# SeismicAccelerometerSystem.net
KiCad netlist of a schematic drawn in EAGLE
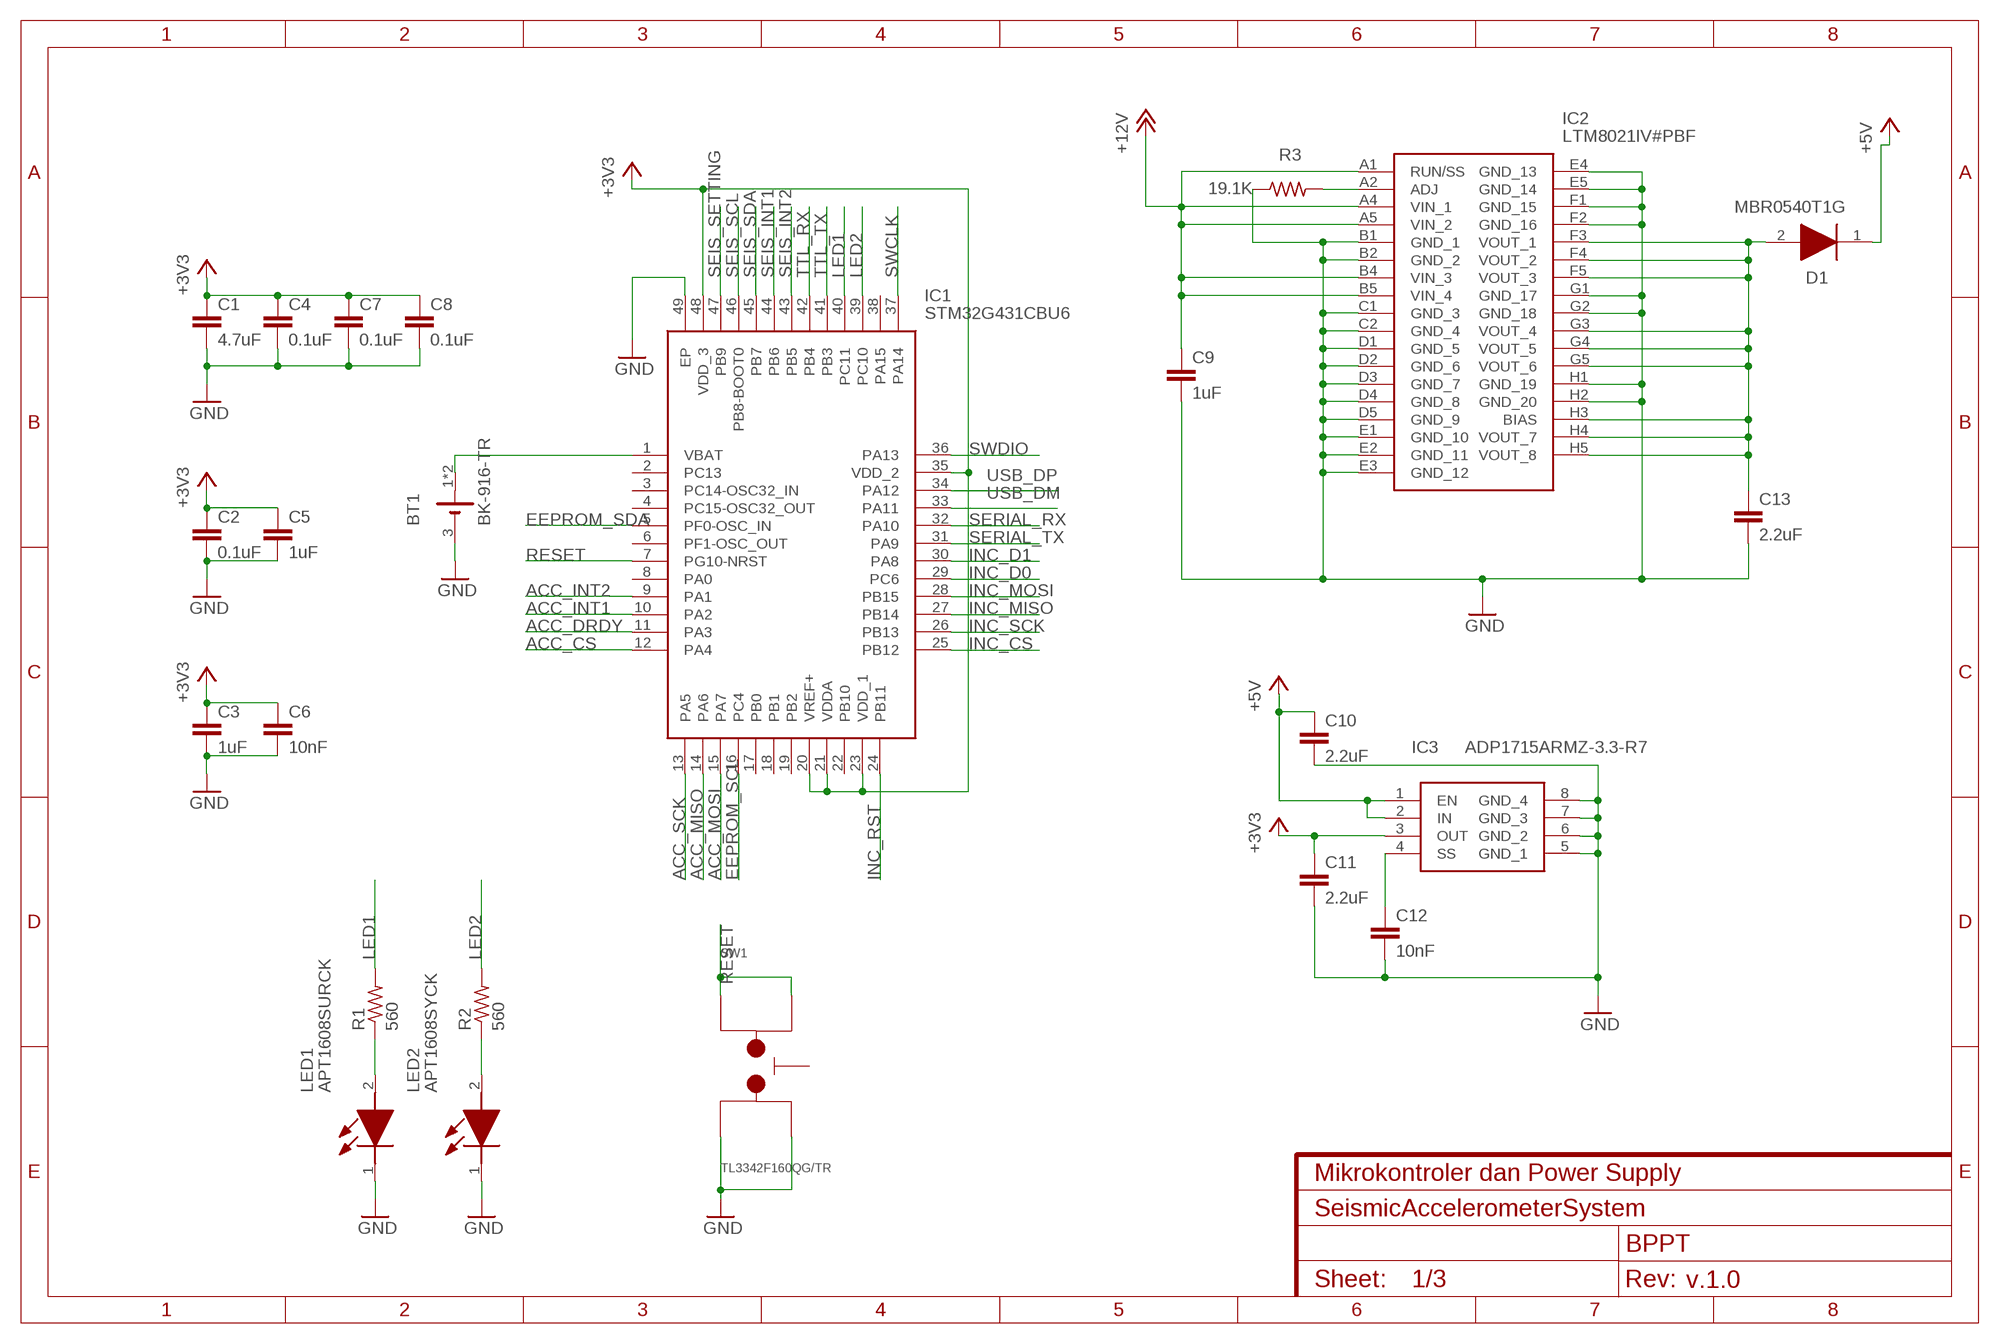
[diagram p0: schematic, sheet 1]
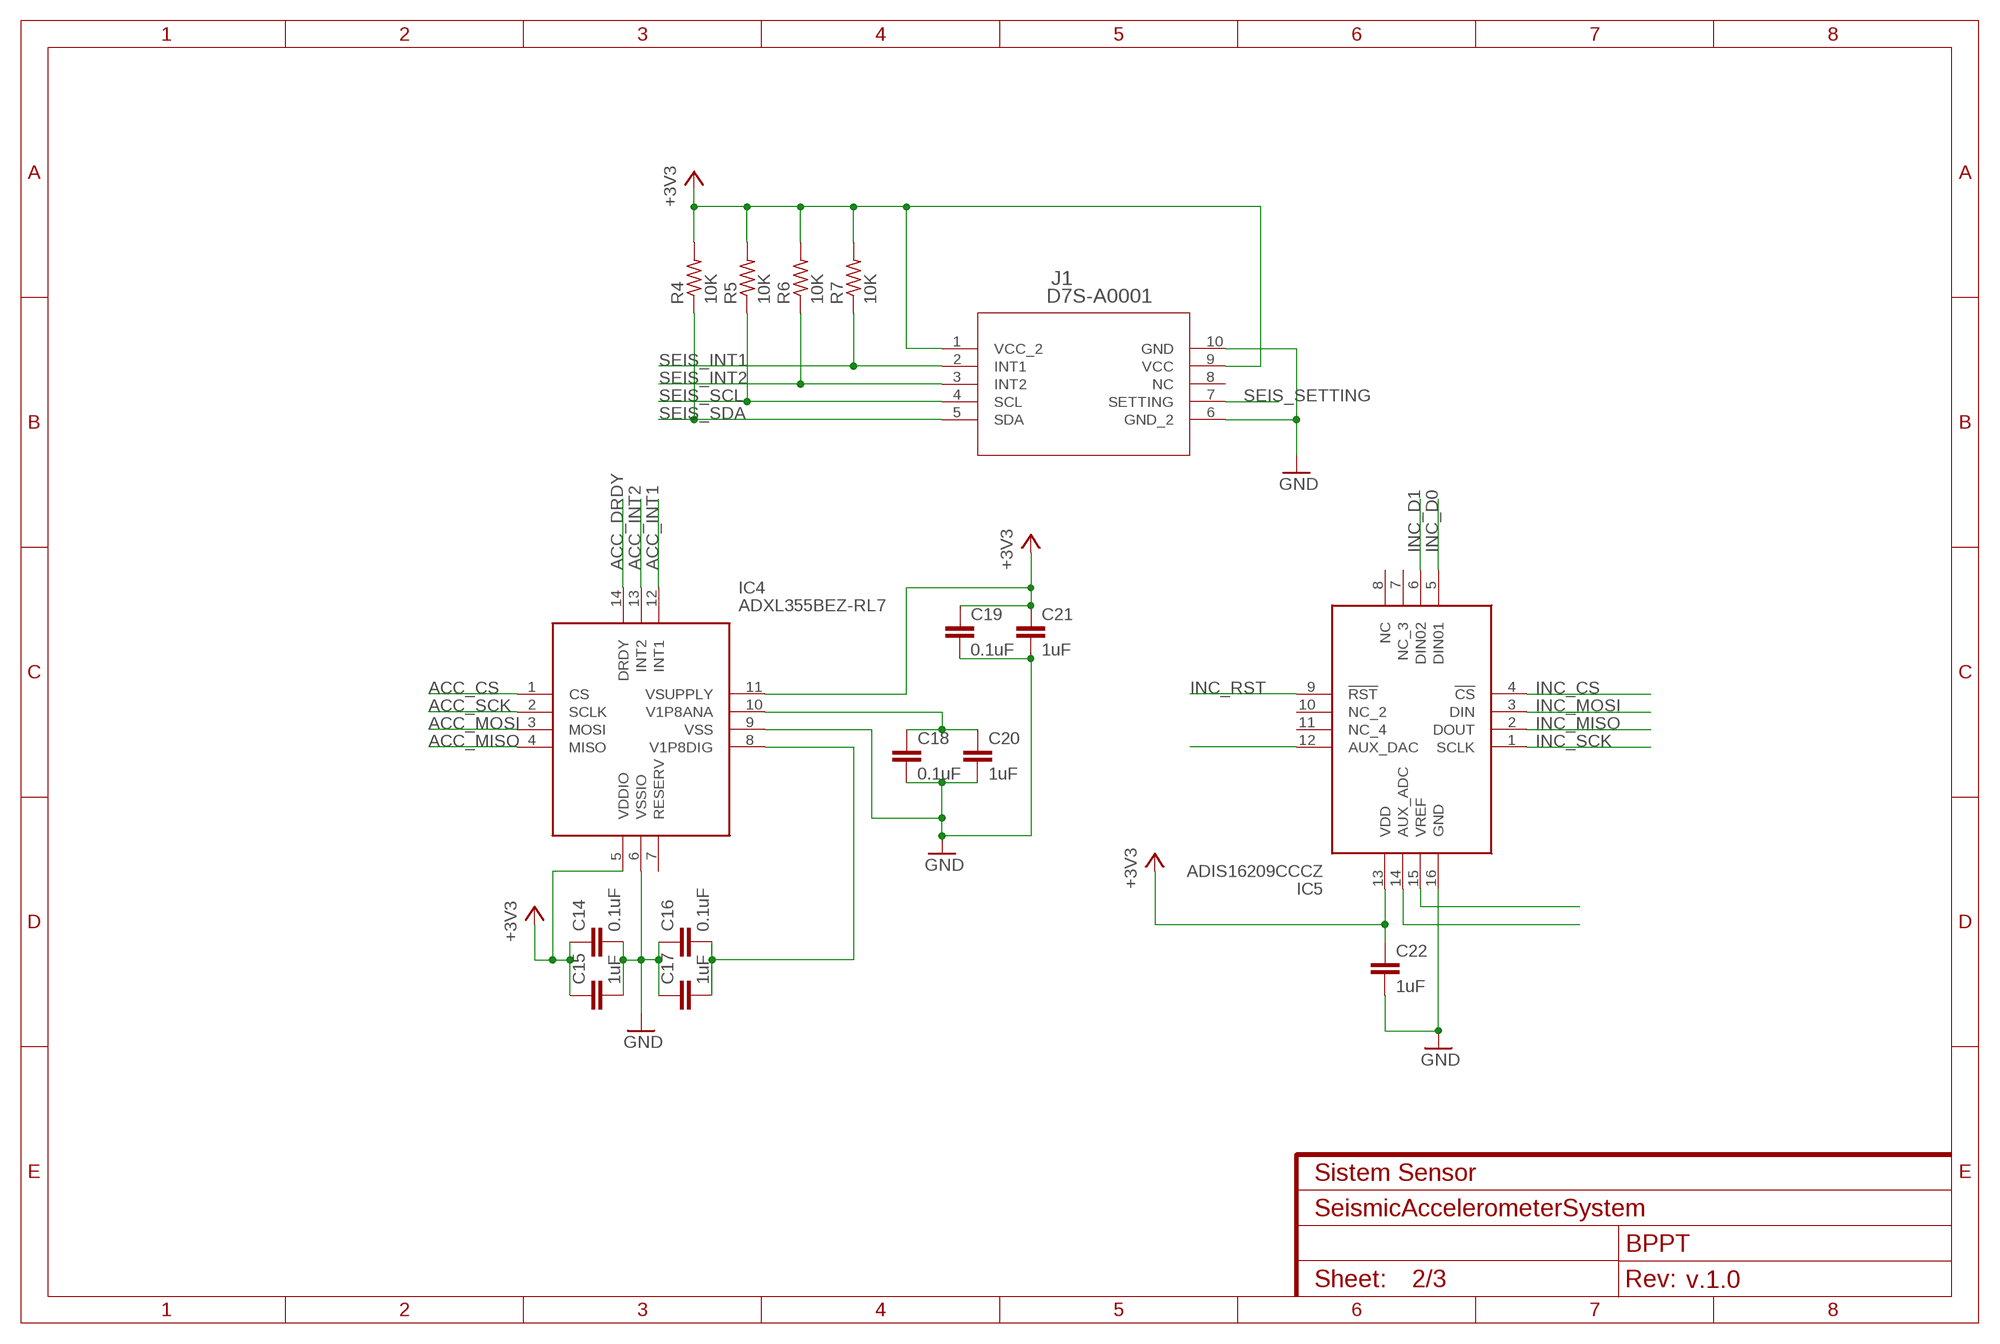
[diagram p1: schematic, sheet 2]
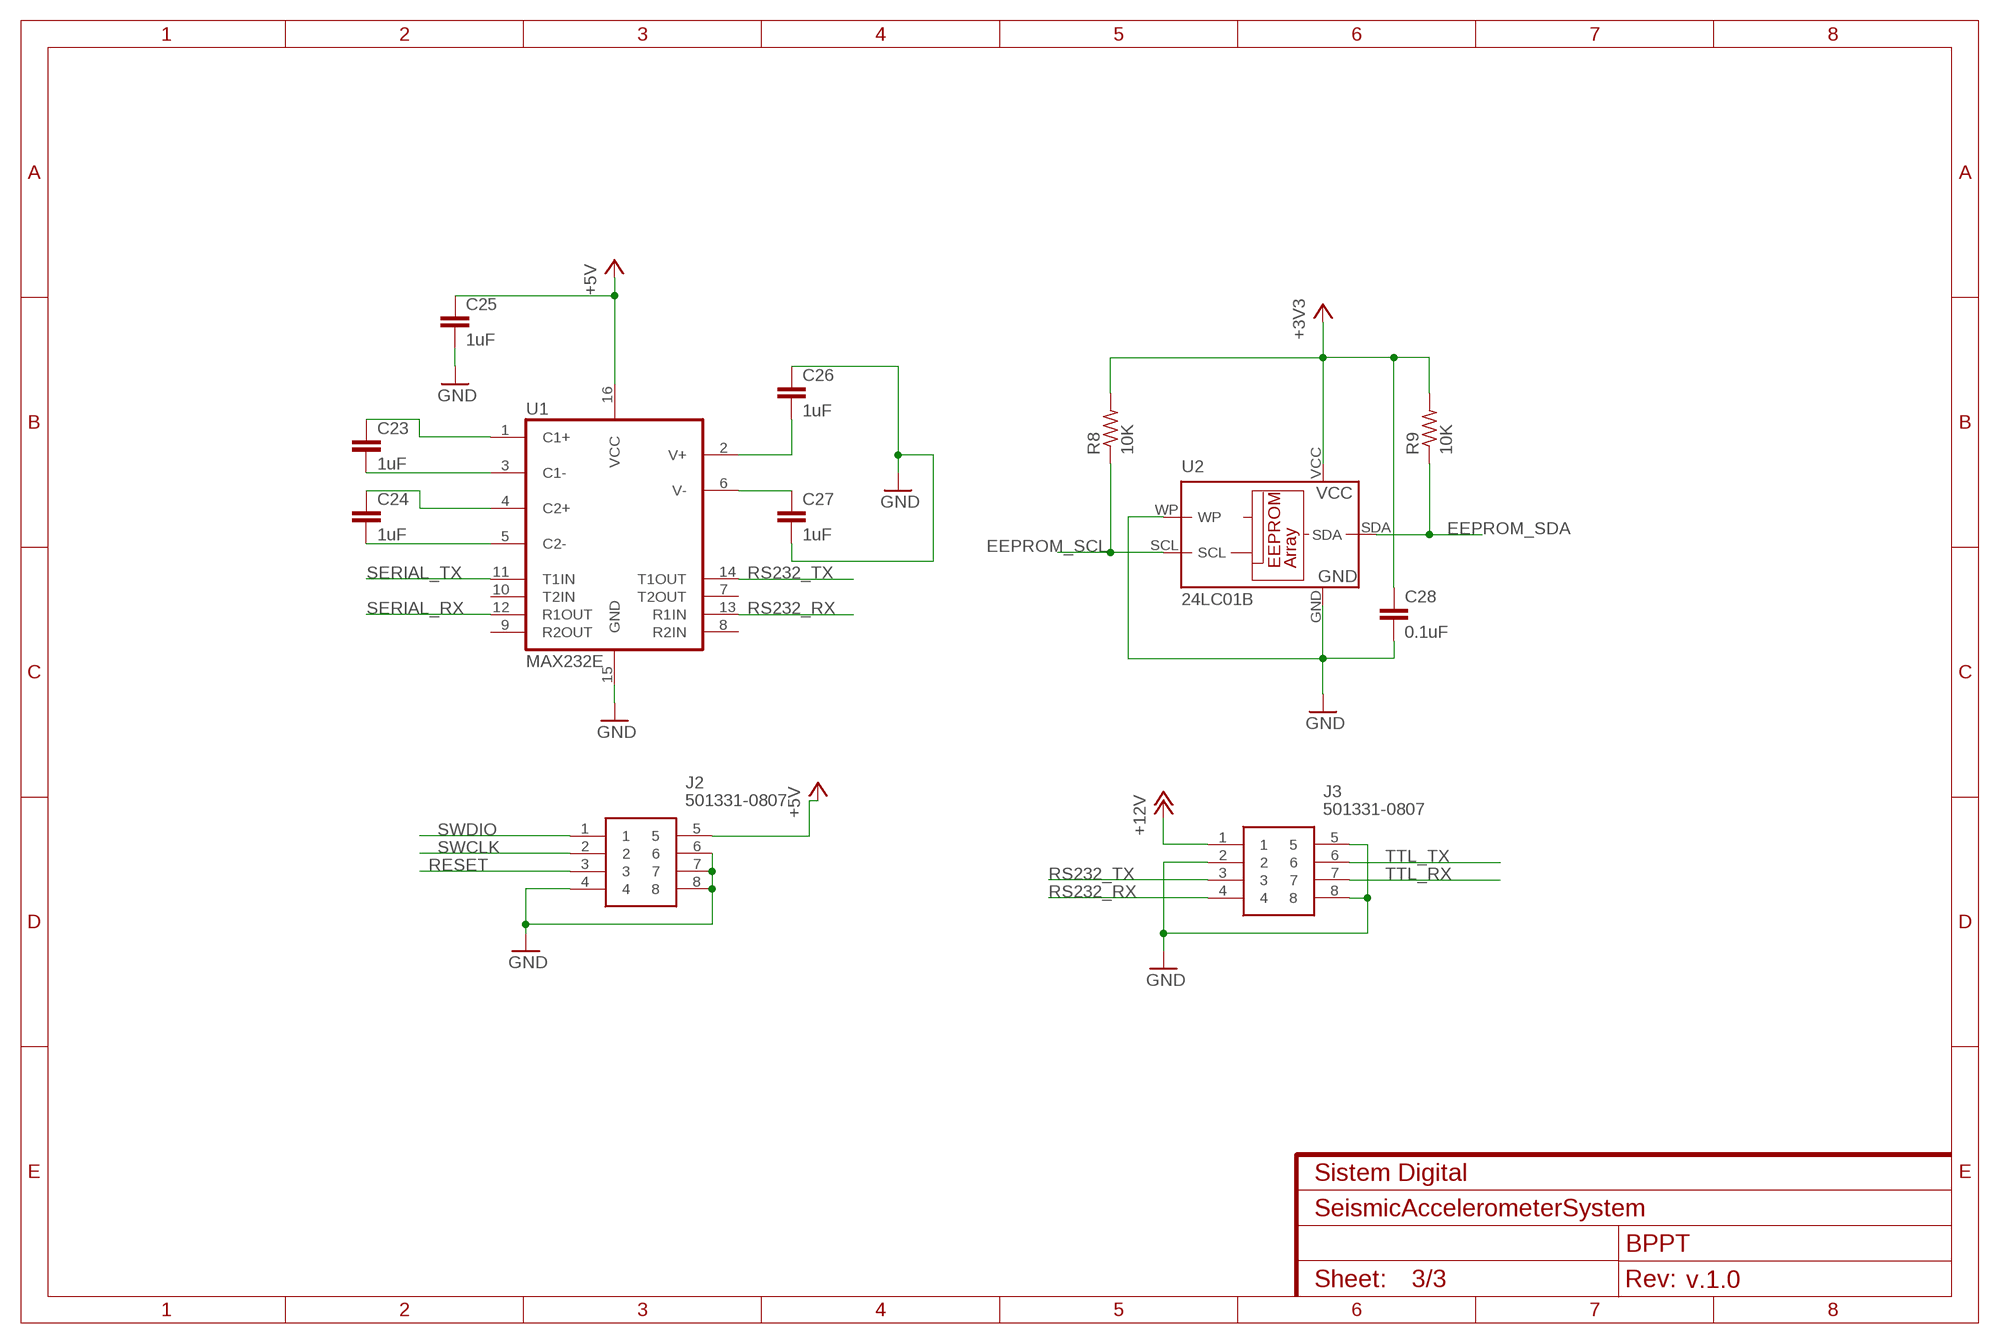
[diagram p2: schematic, sheet 3]

(export (version "E")
  (design (tool "Eeschema 10.0.6"))
  (components
    (comp (ref "C23")
      (value "1uF")
      (footprint "eagle-import:CAPC1608X80N-0603-KEMET")
      (description "CAP CER 1UF 16V X7R 0603")
      (fields (field (name "MANUFACTURERPARTNUMBER") "CGA3E1X7R1C105K080AC"))
      (libsource (lib "eagle-import") (part "C0603-KEMET"))
    )
    (comp (ref "C24")
      (value "1uF")
      (footprint "eagle-import:CAPC1608X80N-0603-KEMET")
      (description "CAP CER 1UF 16V X7R 0603")
      (fields (field (name "MANUFACTURERPARTNUMBER") "CGA3E1X7R1C105K080AC"))
      (libsource (lib "eagle-import") (part "C0603-KEMET"))
    )
    (comp (ref "C25")
      (value "1uF")
      (footprint "eagle-import:CAPC1608X80N-0603-KEMET")
      (description "CAP CER 1UF 16V X7R 0603")
      (fields (field (name "MANUFACTURERPARTNUMBER") "CGA3E1X7R1C105K080AC"))
      (libsource (lib "eagle-import") (part "C0603-KEMET"))
    )
    (comp (ref "C26")
      (value "1uF")
      (footprint "eagle-import:CAPC1608X80N-0603-KEMET")
      (description "CAP CER 1UF 16V X7R 0603")
      (fields (field (name "MANUFACTURERPARTNUMBER") "CGA3E1X7R1C105K080AC"))
      (libsource (lib "eagle-import") (part "C0603-KEMET"))
    )
    (comp (ref "C27")
      (value "1uF")
      (footprint "eagle-import:CAPC1608X80N-0603-KEMET")
      (description "CAP CER 1UF 16V X7R 0603")
      (fields (field (name "MANUFACTURERPARTNUMBER") "CGA3E1X7R1C105K080AC"))
      (libsource (lib "eagle-import") (part "C0603-KEMET"))
    )
    (comp (ref "C28")
      (value "0.1uF")
      (footprint "eagle-import:CAPC1005X50N-0402-KEMET")
      (description "CAP CER 0.1UF 16V Y5V 0402")
      (fields (field (name "MANUFACTURERPARTNUMBER") "C0402C104Z4VAC7867"))
      (libsource (lib "eagle-import") (part "C0402-KEMET"))
    )
    (comp (ref "J2")
      (value "501331-0807")
      (footprint "eagle-import:501331-0807")
      (description "CONN HEADER SMD 8POS 1MM")
      (fields
        (field (name "MOUSER_PART_NUMBER") "538-501331-0807")
        (field (name "MANUFACTURERPARTNUMBER") "5013310807")
      )
      (libsource (lib "eagle-import") (part "501331-0807"))
    )
    (comp (ref "J3")
      (value "501331-0807")
      (footprint "eagle-import:501331-0807")
      (description "CONN HEADER SMD 8POS 1MM")
      (fields
        (field (name "MOUSER_PART_NUMBER") "538-501331-0807")
        (field (name "MANUFACTURERPARTNUMBER") "5013310807")
      )
      (libsource (lib "eagle-import") (part "501331-0807"))
    )
    (comp (ref "R8")
      (value "10K")
      (footprint "eagle-import:RESC1005X35N-0402-VISHAYDALE")
      (description "RES SMD 10K OHM 1% 1/16W 0402")
      (fields (field (name "MANUFACTURERPARTNUMBER") "RC0402FR-0710KL"))
      (libsource (lib "eagle-import") (part "R0402-VISHAYDALE"))
    )
    (comp (ref "R9")
      (value "10K")
      (footprint "eagle-import:RESC1005X35N-0402-VISHAYDALE")
      (description "RES SMD 10K OHM 1% 1/16W 0402")
      (fields (field (name "MANUFACTURERPARTNUMBER") "RC0402FR-0710KL"))
      (libsource (lib "eagle-import") (part "R0402-VISHAYDALE"))
    )
    (comp (ref "U1")
      (value "MAX232E")
      (footprint "eagle-import:SOIC127P1030X265-16N")
      (description "IC TRANSCEIVER FULL 2/2 16SOIC")
      (fields (field (name "MANUFACTURERPARTNUMBER") "MAX232ECDW"))
      (libsource (lib "eagle-import") (part "MAX232E"))
    )
    (comp (ref "U2")
      (value "24LC01B")
      (footprint "eagle-import:SOT23-5L")
      (description "IC EEPROM 1K I2C 400KHZ SOT23-5")
      (fields (field (name "MANUFACTURERPARTNUMBER") "24LC01BT-I/OT"))
      (libsource (lib "eagle-import") (part "24LC01B"))
    )
    (comp (ref "BT1")
      (value "BK-916-TR")
      (footprint "eagle-import:BAT_BK-916-TR")
      (description "BATTERY RETAINER COIN 12MM SMD")
      (fields (field (name "MF") "MPD (Memory Protection Devices)"))
      (libsource (lib "eagle-import") (part "BK-916-TR"))
    )
    (comp (ref "C1")
      (value "4.7uF")
      (footprint "eagle-import:CAPC1608X80N-0603-KEMET")
      (description "CAP CER 4.7UF 6.3V X5R 0603")
      (fields (field (name "MANUFACTURERPARTNUMBER") "C0603C475K9PACTU"))
      (libsource (lib "eagle-import") (part "C0603-KEMET"))
    )
    (comp (ref "C2")
      (value "0.1uF")
      (footprint "eagle-import:CAPC1005X50N-0402-KEMET")
      (description "CAP CER 0.1UF 16V X7R 0402")
      (fields (field (name "MANUFACTURERPARTNUMBER") "C0402C104K4RACTU"))
      (libsource (lib "eagle-import") (part "C0402-KEMET"))
    )
    (comp (ref "C3")
      (value "1uF")
      (footprint "eagle-import:CAPC1005X50N-0402-KEMET")
      (description "1µF ±10% 6.3V Ceramic Capacitor X5R 0402 (1005 Metric)")
      (fields (field (name "MANUFACTURERPARTNUMBER") "CC0402KRX5R5BB105"))
      (libsource (lib "eagle-import") (part "C0402-KEMET"))
    )
    (comp (ref "C4")
      (value "0.1uF")
      (footprint "eagle-import:CAPC1005X50N-0402-KEMET")
      (description "CAP CER 0.1UF 16V X7R 0402")
      (fields (field (name "MANUFACTURERPARTNUMBER") "C0402C104K4RACTU"))
      (libsource (lib "eagle-import") (part "C0402-KEMET"))
    )
    (comp (ref "C5")
      (value "1uF")
      (footprint "eagle-import:CAPC1005X50N-0402-KEMET")
      (description "1µF ±10% 6.3V Ceramic Capacitor X5R 0402 (1005 Metric)")
      (fields (field (name "MANUFACTURERPARTNUMBER") "CC0402KRX5R5BB105"))
      (libsource (lib "eagle-import") (part "C0402-KEMET"))
    )
    (comp (ref "C6")
      (value "10nF")
      (footprint "eagle-import:CAPC1005X50N-0402-KEMET")
      (description "CAP CER 10000PF 25V X7R 0402")
      (fields (field (name "MANUFACTURERPARTNUMBER") "C0402C103K3RACTU"))
      (libsource (lib "eagle-import") (part "C0402-KEMET"))
    )
    (comp (ref "C7")
      (value "0.1uF")
      (footprint "eagle-import:CAPC1005X50N-0402-KEMET")
      (description "CAP CER 0.1UF 16V X7R 0402")
      (fields (field (name "MANUFACTURERPARTNUMBER") "C0402C104K4RACTU"))
      (libsource (lib "eagle-import") (part "C0402-KEMET"))
    )
    (comp (ref "C8")
      (value "0.1uF")
      (footprint "eagle-import:CAPC1005X50N-0402-KEMET")
      (description "CAP CER 0.1UF 16V X7R 0402")
      (fields (field (name "MANUFACTURERPARTNUMBER") "C0402C104K4RACTU"))
      (libsource (lib "eagle-import") (part "C0402-KEMET"))
    )
    (comp (ref "C9")
      (value "1uF")
      (footprint "eagle-import:CAPC2113X90N-0805-KEMET")
      (description "CAP CER 1UF 50V X7R 0805")
      (fields (field (name "MANUFACTURERPARTNUMBER") "C0805C105K5RACTU"))
      (libsource (lib "eagle-import") (part "C0805-KEMET"))
    )
    (comp (ref "C10")
      (value "2.2uF")
      (footprint "eagle-import:CAPC1608X80N-0603-KEMET")
      (description "CAP CER 2.2UF 16V X5R 0603")
      (fields (field (name "MANUFACTURERPARTNUMBER") "C1608X5R1C225K080AB"))
      (libsource (lib "eagle-import") (part "C0603-KEMET"))
    )
    (comp (ref "C11")
      (value "2.2uF")
      (footprint "eagle-import:CAPC1608X80N-0603-KEMET")
      (description "CAP CER 2.2UF 16V X5R 0603")
      (fields (field (name "MANUFACTURERPARTNUMBER") "C1608X5R1C225K080AB"))
      (libsource (lib "eagle-import") (part "C0603-KEMET"))
    )
    (comp (ref "C12")
      (value "10nF")
      (footprint "eagle-import:CAPC1005X50N-0402-KEMET")
      (description "CAP CER 10000PF 16V X7R 0402")
      (fields (field (name "MANUFACTURERPARTNUMBER") "CC0402KRX7R7BB103"))
      (libsource (lib "eagle-import") (part "C0402-KEMET"))
    )
    (comp (ref "C13")
      (value "2.2uF")
      (footprint "eagle-import:CAPC2113X90N-0805-KEMET")
      (description "CAP CER 2.2UF 10V X7R 0805")
      (fields (field (name "MANUFACTURERPARTNUMBER") "C0805C225K8RACTU"))
      (libsource (lib "eagle-import") (part "C0805-KEMET"))
    )
    (comp (ref "D1")
      (value "MBR0540T1G")
      (footprint "eagle-import:SOD3716X135N")
      (fields (field (name "MOUSER_PART_NUMBER") "863-MBR0540T1G"))
      (libsource (lib "eagle-import") (part "MBR0540T1G"))
    )
    (comp (ref "IC1")
      (value "STM32G431CBU6")
      (footprint "eagle-import:QFN50P700X700X65-49N")
      (description "IC MCU 32BIT 128KB FLSH 48UFQFPN")
      (fields (field (name "MOUSER_PART_NUMBER") "511-STM32G431CBU6"))
      (libsource (lib "eagle-import") (part "STM32G431CBU6"))
    )
    (comp (ref "IC2")
      (value "LTM8021IV#PBF")
      (footprint "eagle-import:LTM8021IVPBF")
      (description "DC DC CONVERTER 0.8-5V 500MA")
      (libsource (lib "eagle-import") (part "LTM8021IV#PBF"))
    )
    (comp (ref "IC3")
      (value "ADP1715ARMZ-3.3-R7")
      (footprint "eagle-import:SOP65P490X110-8N")
      (description "IC REG LINEAR 3.3V 500MA 8MSOP")
      (fields (field (name "MOUSER_PART_NUMBER") "584-ADP1715ARMZ3.3R7"))
      (libsource (lib "eagle-import") (part "ADP1715ARMZ-3.3-R7"))
    )
    (comp (ref "LED1")
      (value "APT1608SURCK")
      (footprint "eagle-import:LEDC1608X85N")
      (fields (field (name "MOUSER_PART_NUMBER") "604-APT1608SURCK"))
      (libsource (lib "eagle-import") (part "APT1608SURCK"))
    )
    (comp (ref "LED2")
      (value "APT1608SYCK")
      (footprint "eagle-import:LEDC1608X85N")
      (fields (field (name "MOUSER_PART_NUMBER") "604-APT1608SYCK"))
      (libsource (lib "eagle-import") (part "APT1608SYCK"))
    )
    (comp (ref "R1")
      (value "560")
      (footprint "eagle-import:RESC1005X30N")
      (description "RES SMD 560 OHM 1% 1/5W 0402")
      (fields (field (name "MANUFACTURERPARTNUMBER") "RCS0402560RFKED"))
      (libsource (lib "eagle-import") (part "R0402-TE"))
    )
    (comp (ref "R2")
      (value "560")
      (footprint "eagle-import:RESC1005X30N")
      (description "RES SMD 560 OHM 1% 1/5W 0402")
      (fields (field (name "MANUFACTURERPARTNUMBER") "RCS0402560RFKED"))
      (libsource (lib "eagle-import") (part "R0402-TE"))
    )
    (comp (ref "R3")
      (value "19.1K")
      (footprint "eagle-import:RESC1005X30N")
      (description "RES SMD 19.1K OHM 1% 1/10W 0402")
      (fields (field (name "MANUFACTURERPARTNUMBER") "ERJ-2RKF1912X"))
      (libsource (lib "eagle-import") (part "R0402-TE"))
    )
    (comp (ref "SW1")
      (value "TL3342F160QG/TR")
      (footprint "eagle-import:TL3342F160QG_TR")
      (description "SWITCH TACTILE SPST-NO 0.05A 12V")
      (fields
        (field (name "DIGI_KEY_PART_NUMBER") "EG2531CT-ND")
        (field (name "MANUFACTURER") "E-Switch")
        (field (name "CREATED_BY") "PCBLayout.com")
      )
      (libsource (lib "eagle-import") (part "TL3342F160QG/TR"))
    )
    (comp (ref "C14")
      (value "0.1uF")
      (footprint "eagle-import:CAPC1005X50N-0402-KEMET")
      (description "CAP CER 0.1UF 16V X7R 0402")
      (fields (field (name "MANUFACTURERPARTNUMBER") "C0402C104K4RACTU"))
      (libsource (lib "eagle-import") (part "C0402-KEMET"))
    )
    (comp (ref "C15")
      (value "1uF")
      (footprint "eagle-import:CAPC1005X50N-0402-KEMET")
      (description "CAP CER 1UF 6.3V X5R 0402")
      (fields (field (name "MANUFACTURERPARTNUMBER") "CC0402KRX5R5BB105"))
      (libsource (lib "eagle-import") (part "C0402-KEMET"))
    )
    (comp (ref "C16")
      (value "0.1uF")
      (footprint "eagle-import:CAPC1005X50N-0402-KEMET")
      (description "CAP CER 0.1UF 16V X7R 0402")
      (fields (field (name "MANUFACTURERPARTNUMBER") "C0402C104K4RACTU"))
      (libsource (lib "eagle-import") (part "C0402-KEMET"))
    )
    (comp (ref "C17")
      (value "1uF")
      (footprint "eagle-import:CAPC1005X50N-0402-KEMET")
      (description "CAP CER 1UF 6.3V X5R 0402")
      (fields (field (name "MANUFACTURERPARTNUMBER") "CC0402KRX5R5BB105"))
      (libsource (lib "eagle-import") (part "C0402-KEMET"))
    )
    (comp (ref "C18")
      (value "0.1uF")
      (footprint "eagle-import:CAPC1005X50N-0402-KEMET")
      (description "CAP CER 0.1UF 16V X7R 0402")
      (fields (field (name "MANUFACTURERPARTNUMBER") "C0402C104K4RACTU"))
      (libsource (lib "eagle-import") (part "C0402-KEMET"))
    )
    (comp (ref "C19")
      (value "0.1uF")
      (footprint "eagle-import:CAPC1005X50N-0402-KEMET")
      (description "CAP CER 0.1UF 16V X7R 0402")
      (fields (field (name "MANUFACTURERPARTNUMBER") "C0402C104K4RACTU"))
      (libsource (lib "eagle-import") (part "C0402-KEMET"))
    )
    (comp (ref "C20")
      (value "1uF")
      (footprint "eagle-import:CAPC1005X50N-0402-KEMET")
      (description "CAP CER 1UF 6.3V X5R 0402")
      (fields (field (name "MANUFACTURERPARTNUMBER") "CC0402KRX5R5BB105"))
      (libsource (lib "eagle-import") (part "C0402-KEMET"))
    )
    (comp (ref "C21")
      (value "1uF")
      (footprint "eagle-import:CAPC1005X50N-0402-KEMET")
      (description "CAP CER 1UF 6.3V X5R 0402")
      (fields (field (name "MANUFACTURERPARTNUMBER") "CC0402KRX5R5BB105"))
      (libsource (lib "eagle-import") (part "C0402-KEMET"))
    )
    (comp (ref "C22")
      (value "1uF")
      (footprint "eagle-import:CAPC1005X50N-0402-KEMET")
      (description "CAP CER 0.1UF 16V X7R 0402")
      (fields (field (name "MANUFACTURERPARTNUMBER") "CGA2B1X7R1C104K050BC"))
      (libsource (lib "eagle-import") (part "C0402-KEMET"))
    )
    (comp (ref "IC4")
      (value "ADXL355BEZ-RL7")
      (footprint "eagle-import:ADXL355BEZRL7")
      (description "Accelerometer X, Y, Z Axis ±2g, 4g, 8g 1.5kHz 14-CLCC (6x6)")
      (fields (field (name "MOUSER_PART_NUMBER") "584-ADXL355BEZ-RL7"))
      (libsource (lib "eagle-import") (part "ADXL355BEZ-RL7"))
    )
    (comp (ref "IC5")
      (value "ADIS16209CCCZ")
      (footprint "eagle-import:LGA16R180P4X4_933X933X390")
      (description "IMU ACCEL/INCLINE SPI 16LGA")
      (fields (field (name "MOUSER_PART_NUMBER") "584-ADIS16209CCCZ"))
      (libsource (lib "eagle-import") (part "ADIS16209CCCZ"))
    )
    (comp (ref "J1")
      (value "D7S-A0001")
      (footprint "eagle-import:D7S-A0001_OMR")
      (description "SENSOR SEISMIC 3 AXIS EARTHQUAKE")
      (fields (field (name "COPYRIGHT") "Copyright (C) 2018 Accelerated Designs. All rights reserved"))
      (libsource (lib "eagle-import") (part "D7S-A0001"))
    )
    (comp (ref "R4")
      (value "10K")
      (footprint "eagle-import:RESC1005X30N")
      (description "RES SMD 10K OHM 1% 1/16W 0402")
      (fields (field (name "MANUFACTURERPARTNUMBER") "RC0402FR-0710KL"))
      (libsource (lib "eagle-import") (part "R0402-TE"))
    )
    (comp (ref "R5")
      (value "10K")
      (footprint "eagle-import:RESC1005X30N")
      (description "RES SMD 10K OHM 1% 1/16W 0402")
      (fields (field (name "MANUFACTURERPARTNUMBER") "RC0402FR-0710KL"))
      (libsource (lib "eagle-import") (part "R0402-TE"))
    )
    (comp (ref "R6")
      (value "10K")
      (footprint "eagle-import:RESC1005X30N")
      (description "RES SMD 10K OHM 1% 1/16W 0402")
      (fields (field (name "MANUFACTURERPARTNUMBER") "RC0402FR-0710KL"))
      (libsource (lib "eagle-import") (part "R0402-TE"))
    )
    (comp (ref "R7")
      (value "10K")
      (footprint "eagle-import:RESC1005X30N")
      (description "RES SMD 10K OHM 1% 1/16W 0402")
      (fields (field (name "MANUFACTURERPARTNUMBER") "RC0402FR-0710KL"))
      (libsource (lib "eagle-import") (part "R0402-TE"))
    )
  )
  (nets
    (net (code "1") (name "+3V3") (class "Default")
      (node (ref "C1") (pin "1") (pinfunction "1_1") (pintype "passive"))
      (node (ref "C11") (pin "1") (pinfunction "1_1") (pintype "passive"))
      (node (ref "C14") (pin "1") (pinfunction "1_1") (pintype "passive"))
      (node (ref "C15") (pin "1") (pinfunction "1_1") (pintype "passive"))
      (node (ref "C19") (pin "1") (pinfunction "1_1") (pintype "passive"))
      (node (ref "C2") (pin "1") (pinfunction "1_1") (pintype "passive"))
      (node (ref "C21") (pin "1") (pinfunction "1_1") (pintype "passive"))
      (node (ref "C22") (pin "1") (pinfunction "1_1") (pintype "passive"))
      (node (ref "C28") (pin "1") (pinfunction "1_1") (pintype "passive"))
      (node (ref "C3") (pin "1") (pinfunction "1_1") (pintype "passive"))
      (node (ref "C4") (pin "1") (pinfunction "1_1") (pintype "passive"))
      (node (ref "C5") (pin "1") (pinfunction "1_1") (pintype "passive"))
      (node (ref "C6") (pin "1") (pinfunction "1_1") (pintype "passive"))
      (node (ref "C7") (pin "1") (pinfunction "1_1") (pintype "passive"))
      (node (ref "C8") (pin "1") (pinfunction "1_1") (pintype "passive"))
      (node (ref "IC1") (pin "20") (pinfunction "VREF+_20") (pintype "bidirectional"))
      (node (ref "IC1") (pin "21") (pinfunction "VDDA_21") (pintype "bidirectional"))
      (node (ref "IC1") (pin "23") (pinfunction "VDD_1_23") (pintype "bidirectional"))
      (node (ref "IC1") (pin "35") (pinfunction "VDD_2_35") (pintype "bidirectional"))
      (node (ref "IC1") (pin "48") (pinfunction "VDD_3_48") (pintype "bidirectional"))
      (node (ref "IC3") (pin "3") (pinfunction "OUT_3") (pintype "bidirectional"))
      (node (ref "IC4") (pin "11") (pinfunction "VSUPPLY_11") (pintype "bidirectional"))
      (node (ref "IC4") (pin "5") (pinfunction "VDDIO_5") (pintype "bidirectional"))
      (node (ref "IC5") (pin "13") (pinfunction "VDD_13") (pintype "bidirectional"))
      (node (ref "J1") (pin "1") (pinfunction "VCC_2_1") (pintype "power_in"))
      (node (ref "J1") (pin "9") (pinfunction "VCC_9") (pintype "power_in"))
      (node (ref "R4") (pin "2") (pinfunction "2_2") (pintype "passive"))
      (node (ref "R5") (pin "2") (pinfunction "2_2") (pintype "passive"))
      (node (ref "R6") (pin "2") (pinfunction "2_2") (pintype "passive"))
      (node (ref "R7") (pin "2") (pinfunction "2_2") (pintype "passive"))
      (node (ref "R8") (pin "2") (pinfunction "2_2") (pintype "passive"))
      (node (ref "R9") (pin "2") (pinfunction "2_2") (pintype "passive"))
      (node (ref "U2") (pin "VCC") (pinfunction "VCC_VCC") (pintype "power_in"))
    )
    (net (code "2") (name "+5V") (class "Default")
      (node (ref "C10") (pin "1") (pinfunction "1_1") (pintype "passive"))
      (node (ref "C25") (pin "1") (pinfunction "1_1") (pintype "passive"))
      (node (ref "D1") (pin "1") (pinfunction "K_1") (pintype "bidirectional"))
      (node (ref "IC3") (pin "1") (pinfunction "EN_1") (pintype "bidirectional"))
      (node (ref "IC3") (pin "2") (pinfunction "IN_2") (pintype "bidirectional"))
      (node (ref "J2") (pin "5") (pinfunction "5_5") (pintype "bidirectional"))
      (node (ref "U1") (pin "16") (pinfunction "VCC_16") (pintype "bidirectional"))
    )
    (net (code "3") (name "+12V") (class "Default")
      (node (ref "C9") (pin "1") (pinfunction "1_1") (pintype "passive"))
      (node (ref "IC2") (pin "A1") (pinfunction "RUN/SS_A1") (pintype "bidirectional"))
      (node (ref "IC2") (pin "A4") (pinfunction "VIN_1_A4") (pintype "bidirectional"))
      (node (ref "IC2") (pin "A5") (pinfunction "VIN_2_A5") (pintype "bidirectional"))
      (node (ref "IC2") (pin "B4") (pinfunction "VIN_3_B4") (pintype "bidirectional"))
      (node (ref "IC2") (pin "B5") (pinfunction "VIN_4_B5") (pintype "bidirectional"))
      (node (ref "J3") (pin "1") (pinfunction "1_1") (pintype "bidirectional"))
    )
    (net (code "4") (name "ACC_CS") (class "Default")
      (node (ref "IC1") (pin "12") (pinfunction "PA4_12") (pintype "bidirectional"))
      (node (ref "IC4") (pin "1") (pinfunction "CS_1") (pintype "bidirectional"))
    )
    (net (code "5") (name "ACC_DRDY") (class "Default")
      (node (ref "IC1") (pin "11") (pinfunction "PA3_11") (pintype "bidirectional"))
      (node (ref "IC4") (pin "14") (pinfunction "DRDY_14") (pintype "bidirectional"))
    )
    (net (code "6") (name "ACC_INT1") (class "Default")
      (node (ref "IC1") (pin "10") (pinfunction "PA2_10") (pintype "bidirectional"))
      (node (ref "IC4") (pin "12") (pinfunction "INT1_12") (pintype "bidirectional"))
    )
    (net (code "7") (name "ACC_INT2") (class "Default")
      (node (ref "IC1") (pin "9") (pinfunction "PA1_9") (pintype "bidirectional"))
      (node (ref "IC4") (pin "13") (pinfunction "INT2_13") (pintype "bidirectional"))
    )
    (net (code "8") (name "ACC_MISO") (class "Default")
      (node (ref "IC1") (pin "14") (pinfunction "PA6_14") (pintype "bidirectional"))
      (node (ref "IC4") (pin "4") (pinfunction "MISO_4") (pintype "bidirectional"))
    )
    (net (code "9") (name "ACC_MOSI") (class "Default")
      (node (ref "IC1") (pin "15") (pinfunction "PA7_15") (pintype "bidirectional"))
      (node (ref "IC4") (pin "3") (pinfunction "MOSI_3") (pintype "bidirectional"))
    )
    (net (code "10") (name "ACC_SCK") (class "Default")
      (node (ref "IC1") (pin "13") (pinfunction "PA5_13") (pintype "bidirectional"))
      (node (ref "IC4") (pin "2") (pinfunction "SCLK_2") (pintype "bidirectional"))
    )
    (net (code "11") (name "EEPROM_SCL") (class "Default")
      (node (ref "IC1") (pin "16") (pinfunction "PC4_16") (pintype "bidirectional"))
      (node (ref "R8") (pin "1") (pinfunction "1_1") (pintype "passive"))
      (node (ref "U2") (pin "SCL") (pinfunction "SCL_SCL") (pintype "input"))
    )
    (net (code "12") (name "EEPROM_SDA") (class "Default")
      (node (ref "IC1") (pin "5") (pinfunction "PF0-OSC_IN_5") (pintype "bidirectional"))
      (node (ref "R9") (pin "1") (pinfunction "1_1") (pintype "passive"))
      (node (ref "U2") (pin "SDA") (pinfunction "SDA_SDA") (pintype "bidirectional"))
    )
    (net (code "13") (name "GND") (class "Default")
      (node (ref "BT1") (pin "3") (pinfunction "-_3") (pintype "passive"))
      (node (ref "C1") (pin "2") (pinfunction "2_2") (pintype "passive"))
      (node (ref "C10") (pin "2") (pinfunction "2_2") (pintype "passive"))
      (node (ref "C11") (pin "2") (pinfunction "2_2") (pintype "passive"))
      (node (ref "C12") (pin "2") (pinfunction "2_2") (pintype "passive"))
      (node (ref "C13") (pin "2") (pinfunction "2_2") (pintype "passive"))
      (node (ref "C14") (pin "2") (pinfunction "2_2") (pintype "passive"))
      (node (ref "C15") (pin "2") (pinfunction "2_2") (pintype "passive"))
      (node (ref "C16") (pin "1") (pinfunction "1_1") (pintype "passive"))
      (node (ref "C17") (pin "1") (pinfunction "1_1") (pintype "passive"))
      (node (ref "C18") (pin "2") (pinfunction "2_2") (pintype "passive"))
      (node (ref "C19") (pin "2") (pinfunction "2_2") (pintype "passive"))
      (node (ref "C2") (pin "2") (pinfunction "2_2") (pintype "passive"))
      (node (ref "C20") (pin "2") (pinfunction "2_2") (pintype "passive"))
      (node (ref "C21") (pin "2") (pinfunction "2_2") (pintype "passive"))
      (node (ref "C22") (pin "2") (pinfunction "2_2") (pintype "passive"))
      (node (ref "C25") (pin "2") (pinfunction "2_2") (pintype "passive"))
      (node (ref "C26") (pin "1") (pinfunction "1_1") (pintype "passive"))
      (node (ref "C27") (pin "2") (pinfunction "2_2") (pintype "passive"))
      (node (ref "C28") (pin "2") (pinfunction "2_2") (pintype "passive"))
      (node (ref "C3") (pin "2") (pinfunction "2_2") (pintype "passive"))
      (node (ref "C4") (pin "2") (pinfunction "2_2") (pintype "passive"))
      (node (ref "C5") (pin "2") (pinfunction "2_2") (pintype "passive"))
      (node (ref "C6") (pin "2") (pinfunction "2_2") (pintype "passive"))
      (node (ref "C7") (pin "2") (pinfunction "2_2") (pintype "passive"))
      (node (ref "C8") (pin "2") (pinfunction "2_2") (pintype "passive"))
      (node (ref "C9") (pin "2") (pinfunction "2_2") (pintype "passive"))
      (node (ref "IC1") (pin "49") (pinfunction "EP_49") (pintype "bidirectional"))
      (node (ref "IC2") (pin "B1") (pinfunction "GND_1_B1") (pintype "bidirectional"))
      (node (ref "IC2") (pin "B2") (pinfunction "GND_2_B2") (pintype "bidirectional"))
      (node (ref "IC2") (pin "C1") (pinfunction "GND_3_C1") (pintype "bidirectional"))
      (node (ref "IC2") (pin "C2") (pinfunction "GND_4_C2") (pintype "bidirectional"))
      (node (ref "IC2") (pin "D1") (pinfunction "GND_5_D1") (pintype "bidirectional"))
      (node (ref "IC2") (pin "D2") (pinfunction "GND_6_D2") (pintype "bidirectional"))
      (node (ref "IC2") (pin "D3") (pinfunction "GND_7_D3") (pintype "bidirectional"))
      (node (ref "IC2") (pin "D4") (pinfunction "GND_8_D4") (pintype "bidirectional"))
      (node (ref "IC2") (pin "D5") (pinfunction "GND_9_D5") (pintype "bidirectional"))
      (node (ref "IC2") (pin "E1") (pinfunction "GND_10_E1") (pintype "bidirectional"))
      (node (ref "IC2") (pin "E2") (pinfunction "GND_11_E2") (pintype "bidirectional"))
      (node (ref "IC2") (pin "E3") (pinfunction "GND_12_E3") (pintype "bidirectional"))
      (node (ref "IC2") (pin "E4") (pinfunction "GND_13_E4") (pintype "bidirectional"))
      (node (ref "IC2") (pin "E5") (pinfunction "GND_14_E5") (pintype "bidirectional"))
      (node (ref "IC2") (pin "F1") (pinfunction "GND_15_F1") (pintype "bidirectional"))
      (node (ref "IC2") (pin "F2") (pinfunction "GND_16_F2") (pintype "bidirectional"))
      (node (ref "IC2") (pin "G1") (pinfunction "GND_17_G1") (pintype "bidirectional"))
      (node (ref "IC2") (pin "G2") (pinfunction "GND_18_G2") (pintype "bidirectional"))
      (node (ref "IC2") (pin "H1") (pinfunction "GND_19_H1") (pintype "bidirectional"))
      (node (ref "IC2") (pin "H2") (pinfunction "GND_20_H2") (pintype "bidirectional"))
      (node (ref "IC3") (pin "5") (pinfunction "GND_1_5") (pintype "bidirectional"))
      (node (ref "IC3") (pin "6") (pinfunction "GND_2_6") (pintype "bidirectional"))
      (node (ref "IC3") (pin "7") (pinfunction "GND_3_7") (pintype "bidirectional"))
      (node (ref "IC3") (pin "8") (pinfunction "GND_4_8") (pintype "bidirectional"))
      (node (ref "IC4") (pin "6") (pinfunction "VSSIO_6") (pintype "bidirectional"))
      (node (ref "IC4") (pin "9") (pinfunction "VSS_9") (pintype "bidirectional"))
      (node (ref "IC5") (pin "16") (pinfunction "GND_16") (pintype "bidirectional"))
      (node (ref "J1") (pin "10") (pinfunction "GND_10") (pintype "passive"))
      (node (ref "J1") (pin "6") (pinfunction "GND_2_6") (pintype "passive"))
      (node (ref "J2") (pin "4") (pinfunction "4_4") (pintype "bidirectional"))
      (node (ref "J2") (pin "6") (pinfunction "6_6") (pintype "bidirectional"))
      (node (ref "J2") (pin "7") (pinfunction "7_7") (pintype "bidirectional"))
      (node (ref "J2") (pin "8") (pinfunction "8_8") (pintype "bidirectional"))
      (node (ref "J3") (pin "2") (pinfunction "2_2") (pintype "bidirectional"))
      (node (ref "J3") (pin "5") (pinfunction "5_5") (pintype "bidirectional"))
      (node (ref "J3") (pin "8") (pinfunction "8_8") (pintype "bidirectional"))
      (node (ref "LED1") (pin "1") (pinfunction "K_1") (pintype "bidirectional"))
      (node (ref "LED2") (pin "1") (pinfunction "K_1") (pintype "bidirectional"))
      (node (ref "R3") (pin "1") (pinfunction "1_1") (pintype "passive"))
      (node (ref "SW1") (pin "1") (pinfunction "1_1") (pintype "passive"))
      (node (ref "SW1") (pin "2") (pinfunction "2_2") (pintype "passive"))
      (node (ref "U1") (pin "15") (pinfunction "GND_15") (pintype "bidirectional"))
      (node (ref "U2") (pin "GND") (pinfunction "GND_GND") (pintype "power_in"))
      (node (ref "U2") (pin "WP") (pinfunction "WP_WP") (pintype "input"))
    )
    (net (code "14") (name "INC_CS") (class "Default")
      (node (ref "IC1") (pin "25") (pinfunction "PB12_25") (pintype "bidirectional"))
      (node (ref "IC5") (pin "4") (pinfunction "~{CS}_4") (pintype "bidirectional"))
    )
    (net (code "15") (name "INC_D0") (class "Default")
      (node (ref "IC1") (pin "29") (pinfunction "PC6_29") (pintype "bidirectional"))
      (node (ref "IC5") (pin "5") (pinfunction "DIN01_5") (pintype "bidirectional"))
    )
    (net (code "16") (name "INC_D1") (class "Default")
      (node (ref "IC1") (pin "30") (pinfunction "PA8_30") (pintype "bidirectional"))
      (node (ref "IC5") (pin "6") (pinfunction "DIN02_6") (pintype "bidirectional"))
    )
    (net (code "17") (name "INC_MISO") (class "Default")
      (node (ref "IC1") (pin "27") (pinfunction "PB14_27") (pintype "bidirectional"))
      (node (ref "IC5") (pin "2") (pinfunction "DOUT_2") (pintype "bidirectional"))
    )
    (net (code "18") (name "INC_MOSI") (class "Default")
      (node (ref "IC1") (pin "28") (pinfunction "PB15_28") (pintype "bidirectional"))
      (node (ref "IC5") (pin "3") (pinfunction "DIN_3") (pintype "bidirectional"))
    )
    (net (code "19") (name "INC_RST") (class "Default")
      (node (ref "IC1") (pin "24") (pinfunction "PB11_24") (pintype "bidirectional"))
      (node (ref "IC5") (pin "9") (pinfunction "~{RST}_9") (pintype "bidirectional"))
    )
    (net (code "20") (name "INC_SCK") (class "Default")
      (node (ref "IC1") (pin "26") (pinfunction "PB13_26") (pintype "bidirectional"))
      (node (ref "IC5") (pin "1") (pinfunction "SCLK_1") (pintype "bidirectional"))
    )
    (net (code "21") (name "LED1") (class "Default")
      (node (ref "IC1") (pin "40") (pinfunction "PC11_40") (pintype "bidirectional"))
      (node (ref "R1") (pin "2") (pinfunction "2_2") (pintype "passive"))
    )
    (net (code "22") (name "LED2") (class "Default")
      (node (ref "IC1") (pin "39") (pinfunction "PC10_39") (pintype "bidirectional"))
      (node (ref "R2") (pin "2") (pinfunction "2_2") (pintype "passive"))
    )
    (net (code "23") (name "Net-(D1-A)") (class "Default")
      (node (ref "C13") (pin "1") (pinfunction "1_1") (pintype "passive"))
      (node (ref "D1") (pin "2") (pinfunction "A_2") (pintype "bidirectional"))
      (node (ref "IC2") (pin "F3") (pinfunction "VOUT_1_F3") (pintype "bidirectional"))
      (node (ref "IC2") (pin "F4") (pinfunction "VOUT_2_F4") (pintype "bidirectional"))
      (node (ref "IC2") (pin "F5") (pinfunction "VOUT_3_F5") (pintype "bidirectional"))
      (node (ref "IC2") (pin "G3") (pinfunction "VOUT_4_G3") (pintype "bidirectional"))
      (node (ref "IC2") (pin "G4") (pinfunction "VOUT_5_G4") (pintype "bidirectional"))
      (node (ref "IC2") (pin "G5") (pinfunction "VOUT_6_G5") (pintype "bidirectional"))
      (node (ref "IC2") (pin "H3") (pinfunction "BIAS_H3") (pintype "bidirectional"))
      (node (ref "IC2") (pin "H4") (pinfunction "VOUT_7_H4") (pintype "bidirectional"))
      (node (ref "IC2") (pin "H5") (pinfunction "VOUT_8_H5") (pintype "bidirectional"))
    )
    (net (code "24") (name "Net-(IC1-VBAT)") (class "Default")
      (node (ref "BT1") (pin "1") (pinfunction "+_1") (pintype "passive"))
      (node (ref "BT1") (pin "2") (pinfunction "+_2") (pintype "passive"))
      (node (ref "IC1") (pin "1") (pinfunction "VBAT_1") (pintype "bidirectional"))
    )
    (net (code "25") (name "Net-(IC2-ADJ)") (class "Default")
      (node (ref "IC2") (pin "A2") (pinfunction "ADJ_A2") (pintype "bidirectional"))
      (node (ref "R3") (pin "2") (pinfunction "2_2") (pintype "passive"))
    )
    (net (code "26") (name "Net-(IC3-SS)") (class "Default")
      (node (ref "C12") (pin "1") (pinfunction "1_1") (pintype "passive"))
      (node (ref "IC3") (pin "4") (pinfunction "SS_4") (pintype "bidirectional"))
    )
    (net (code "27") (name "Net-(IC4-V1P8ANA)") (class "Default")
      (node (ref "C18") (pin "1") (pinfunction "1_1") (pintype "passive"))
      (node (ref "C20") (pin "1") (pinfunction "1_1") (pintype "passive"))
      (node (ref "IC4") (pin "10") (pinfunction "V1P8ANA_10") (pintype "bidirectional"))
    )
    (net (code "28") (name "Net-(IC4-V1P8DIG)") (class "Default")
      (node (ref "C16") (pin "2") (pinfunction "2_2") (pintype "passive"))
      (node (ref "C17") (pin "2") (pinfunction "2_2") (pintype "passive"))
      (node (ref "IC4") (pin "8") (pinfunction "V1P8DIG_8") (pintype "bidirectional"))
    )
    (net (code "29") (name "Net-(LED1-A)") (class "Default")
      (node (ref "LED1") (pin "2") (pinfunction "A_2") (pintype "bidirectional"))
      (node (ref "R1") (pin "1") (pinfunction "1_1") (pintype "passive"))
    )
    (net (code "30") (name "Net-(LED2-A)") (class "Default")
      (node (ref "LED2") (pin "2") (pinfunction "A_2") (pintype "bidirectional"))
      (node (ref "R2") (pin "1") (pinfunction "1_1") (pintype "passive"))
    )
    (net (code "31") (name "Net-(U1-C1+)") (class "Default")
      (node (ref "C23") (pin "1") (pinfunction "1_1") (pintype "passive"))
      (node (ref "U1") (pin "1") (pinfunction "C1+_1") (pintype "bidirectional"))
    )
    (net (code "32") (name "Net-(U1-C1-)") (class "Default")
      (node (ref "C23") (pin "2") (pinfunction "2_2") (pintype "passive"))
      (node (ref "U1") (pin "3") (pinfunction "C1-_3") (pintype "bidirectional"))
    )
    (net (code "33") (name "Net-(U1-C2+)") (class "Default")
      (node (ref "C24") (pin "1") (pinfunction "1_1") (pintype "passive"))
      (node (ref "U1") (pin "4") (pinfunction "C2+_4") (pintype "bidirectional"))
    )
    (net (code "34") (name "Net-(U1-C2-)") (class "Default")
      (node (ref "C24") (pin "2") (pinfunction "2_2") (pintype "passive"))
      (node (ref "U1") (pin "5") (pinfunction "C2-_5") (pintype "bidirectional"))
    )
    (net (code "35") (name "Net-(U1-V+)") (class "Default")
      (node (ref "C26") (pin "2") (pinfunction "2_2") (pintype "passive"))
      (node (ref "U1") (pin "2") (pinfunction "V+_2") (pintype "bidirectional"))
    )
    (net (code "36") (name "Net-(U1-V-)") (class "Default")
      (node (ref "C27") (pin "1") (pinfunction "1_1") (pintype "passive"))
      (node (ref "U1") (pin "6") (pinfunction "V-_6") (pintype "bidirectional"))
    )
    (net (code "37") (name "RESET") (class "Default")
      (node (ref "IC1") (pin "7") (pinfunction "PG10-NRST_7") (pintype "bidirectional"))
      (node (ref "J2") (pin "3") (pinfunction "3_3") (pintype "bidirectional"))
      (node (ref "SW1") (pin "3") (pinfunction "3_3") (pintype "passive"))
      (node (ref "SW1") (pin "4") (pinfunction "4_4") (pintype "passive"))
    )
    (net (code "38") (name "RS232_RX") (class "Default")
      (node (ref "J3") (pin "4") (pinfunction "4_4") (pintype "bidirectional"))
      (node (ref "U1") (pin "13") (pinfunction "R1IN_13") (pintype "input"))
    )
    (net (code "39") (name "RS232_TX") (class "Default")
      (node (ref "J3") (pin "3") (pinfunction "3_3") (pintype "bidirectional"))
      (node (ref "U1") (pin "14") (pinfunction "T1OUT_14") (pintype "output"))
    )
    (net (code "40") (name "SEIS_INT1") (class "Default")
      (node (ref "IC1") (pin "44") (pinfunction "PB6_44") (pintype "bidirectional"))
      (node (ref "J1") (pin "2") (pinfunction "INT1_2") (pintype "output"))
      (node (ref "R7") (pin "1") (pinfunction "1_1") (pintype "passive"))
    )
    (net (code "41") (name "SEIS_INT2") (class "Default")
      (node (ref "IC1") (pin "43") (pinfunction "PB5_43") (pintype "bidirectional"))
      (node (ref "J1") (pin "3") (pinfunction "INT2_3") (pintype "output"))
      (node (ref "R6") (pin "1") (pinfunction "1_1") (pintype "passive"))
    )
    (net (code "42") (name "SEIS_SCL") (class "Default")
      (node (ref "IC1") (pin "46") (pinfunction "PB8-BOOT0_46") (pintype "bidirectional"))
      (node (ref "J1") (pin "4") (pinfunction "SCL_4") (pintype "input"))
      (node (ref "R5") (pin "1") (pinfunction "1_1") (pintype "passive"))
    )
    (net (code "43") (name "SEIS_SDA") (class "Default")
      (node (ref "IC1") (pin "45") (pinfunction "PB7_45") (pintype "bidirectional"))
      (node (ref "J1") (pin "5") (pinfunction "SDA_5") (pintype "bidirectional"))
      (node (ref "R4") (pin "1") (pinfunction "1_1") (pintype "passive"))
    )
    (net (code "44") (name "SEIS_SETTING") (class "Default")
      (node (ref "IC1") (pin "47") (pinfunction "PB9_47") (pintype "bidirectional"))
      (node (ref "J1") (pin "7") (pinfunction "SETTING_7") (pintype "input"))
    )
    (net (code "45") (name "SERIAL_RX") (class "Default")
      (node (ref "IC1") (pin "32") (pinfunction "PA10_32") (pintype "bidirectional"))
      (node (ref "U1") (pin "12") (pinfunction "R1OUT_12") (pintype "output"))
    )
    (net (code "46") (name "SERIAL_TX") (class "Default")
      (node (ref "IC1") (pin "31") (pinfunction "PA9_31") (pintype "bidirectional"))
      (node (ref "U1") (pin "11") (pinfunction "T1IN_11") (pintype "input"))
    )
    (net (code "47") (name "SWCLK") (class "Default")
      (node (ref "IC1") (pin "37") (pinfunction "PA14_37") (pintype "bidirectional"))
      (node (ref "J2") (pin "2") (pinfunction "2_2") (pintype "bidirectional"))
    )
    (net (code "48") (name "SWDIO") (class "Default")
      (node (ref "IC1") (pin "36") (pinfunction "PA13_36") (pintype "bidirectional"))
      (node (ref "J2") (pin "1") (pinfunction "1_1") (pintype "bidirectional"))
    )
    (net (code "49") (name "TTL_RX") (class "Default")
      (node (ref "IC1") (pin "42") (pinfunction "PB4_42") (pintype "bidirectional"))
      (node (ref "J3") (pin "7") (pinfunction "7_7") (pintype "bidirectional"))
    )
    (net (code "50") (name "TTL_TX") (class "Default")
      (node (ref "IC1") (pin "41") (pinfunction "PB3_41") (pintype "bidirectional"))
      (node (ref "J3") (pin "6") (pinfunction "6_6") (pintype "bidirectional"))
    )
    (net (code "51") (name "USB_DM") (class "Default")
      (node (ref "IC1") (pin "33") (pinfunction "PA11_33") (pintype "bidirectional"))
    )
    (net (code "52") (name "USB_DP") (class "Default")
      (node (ref "IC1") (pin "34") (pinfunction "PA12_34") (pintype "bidirectional"))
    )
    (net (code "53") (name "unconnected-(IC1-PA0-Pad8)") (class "Default")
      (node (ref "IC1") (pin "8") (pinfunction "PA0_8") (pintype "bidirectional"))
    )
    (net (code "54") (name "unconnected-(IC1-PA15-Pad38)") (class "Default")
      (node (ref "IC1") (pin "38") (pinfunction "PA15_38") (pintype "bidirectional"))
    )
    (net (code "55") (name "unconnected-(IC1-PB0-Pad17)") (class "Default")
      (node (ref "IC1") (pin "17") (pinfunction "PB0_17") (pintype "bidirectional"))
    )
    (net (code "56") (name "unconnected-(IC1-PB1-Pad18)") (class "Default")
      (node (ref "IC1") (pin "18") (pinfunction "PB1_18") (pintype "bidirectional"))
    )
    (net (code "57") (name "unconnected-(IC1-PB2-Pad19)") (class "Default")
      (node (ref "IC1") (pin "19") (pinfunction "PB2_19") (pintype "bidirectional"))
    )
    (net (code "58") (name "unconnected-(IC1-PB10-Pad22)") (class "Default")
      (node (ref "IC1") (pin "22") (pinfunction "PB10_22") (pintype "bidirectional"))
    )
    (net (code "59") (name "unconnected-(IC1-PC13-Pad2)") (class "Default")
      (node (ref "IC1") (pin "2") (pinfunction "PC13_2") (pintype "bidirectional"))
    )
    (net (code "60") (name "unconnected-(IC1-PC14-OSC32_IN-Pad3)") (class "Default")
      (node (ref "IC1") (pin "3") (pinfunction "PC14-OSC32_IN_3") (pintype "bidirectional"))
    )
    (net (code "61") (name "unconnected-(IC1-PC15-OSC32_OUT-Pad4)") (class "Default")
      (node (ref "IC1") (pin "4") (pinfunction "PC15-OSC32_OUT_4") (pintype "bidirectional"))
    )
    (net (code "62") (name "unconnected-(IC1-PF1-OSC_OUT-Pad6)") (class "Default")
      (node (ref "IC1") (pin "6") (pinfunction "PF1-OSC_OUT_6") (pintype "bidirectional"))
    )
    (net (code "63") (name "unconnected-(IC4-RESERV-Pad7)") (class "Default")
      (node (ref "IC4") (pin "7") (pinfunction "RESERV_7") (pintype "bidirectional"))
    )
    (net (code "64") (name "unconnected-(IC5-AUX_ADC-Pad14)") (class "Default")
      (node (ref "IC5") (pin "14") (pinfunction "AUX_ADC_14") (pintype "bidirectional"))
    )
    (net (code "65") (name "unconnected-(IC5-AUX_DAC-Pad12)") (class "Default")
      (node (ref "IC5") (pin "12") (pinfunction "AUX_DAC_12") (pintype "bidirectional"))
    )
    (net (code "66") (name "unconnected-(IC5-NC-Pad8)") (class "Default")
      (node (ref "IC5") (pin "8") (pinfunction "NC_8") (pintype "no_connect"))
    )
    (net (code "67") (name "unconnected-(IC5-NC_2-Pad10)") (class "Default")
      (node (ref "IC5") (pin "10") (pinfunction "NC_2_10") (pintype "bidirectional"))
    )
    (net (code "68") (name "unconnected-(IC5-NC_3-Pad7)") (class "Default")
      (node (ref "IC5") (pin "7") (pinfunction "NC_3_7") (pintype "bidirectional"))
    )
    (net (code "69") (name "unconnected-(IC5-NC_4-Pad11)") (class "Default")
      (node (ref "IC5") (pin "11") (pinfunction "NC_4_11") (pintype "bidirectional"))
    )
    (net (code "70") (name "unconnected-(IC5-VREF-Pad15)") (class "Default")
      (node (ref "IC5") (pin "15") (pinfunction "VREF_15") (pintype "bidirectional"))
    )
    (net (code "71") (name "unconnected-(J1-NC-Pad8)") (class "Default")
      (node (ref "J1") (pin "8") (pinfunction "NC_8") (pintype "no_connect"))
    )
    (net (code "72") (name "unconnected-(U1-R2IN-Pad8)") (class "Default")
      (node (ref "U1") (pin "8") (pinfunction "R2IN_8") (pintype "input"))
    )
    (net (code "73") (name "unconnected-(U1-R2OUT-Pad9)") (class "Default")
      (node (ref "U1") (pin "9") (pinfunction "R2OUT_9") (pintype "output"))
    )
    (net (code "74") (name "unconnected-(U1-T2IN-Pad10)") (class "Default")
      (node (ref "U1") (pin "10") (pinfunction "T2IN_10") (pintype "input"))
    )
    (net (code "75") (name "unconnected-(U1-T2OUT-Pad7)") (class "Default")
      (node (ref "U1") (pin "7") (pinfunction "T2OUT_7") (pintype "output"))
    )
  )
)
